# 03-_-.net
KiCad netlist of a schematic drawn in Altium Designer
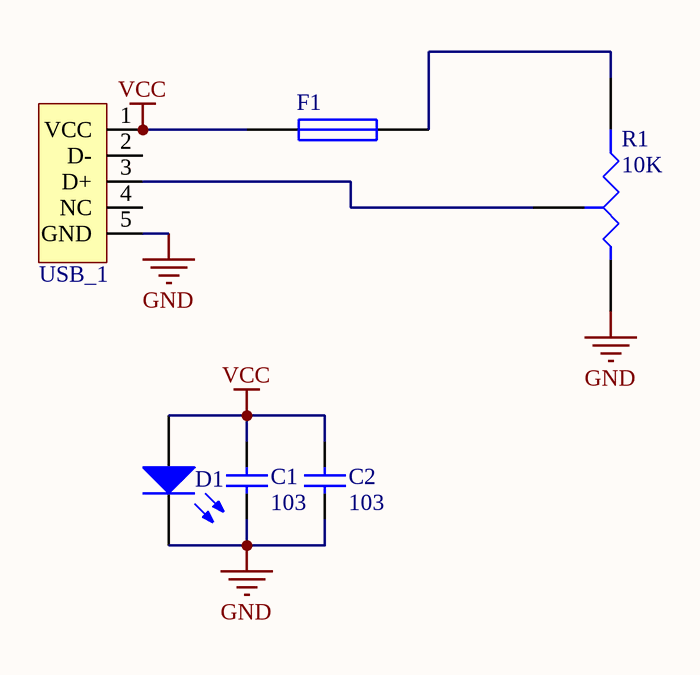
[diagram p0: 03-旋钮模块-原理图.SchDoc]

(export (version "E")
  (design (tool "Eeschema 10.0.6"))
  (components
    (comp (ref "C1")
      (value "103")
      (footprint "0805")
      (description "Capacitor")
      (fields (field (name "Comment") "Cap") (field (name "PUBLISHER") "Altium Limited"))
      (libsource (lib "Miscellaneous Devices") (part "Cap"))
    )
    (comp (ref "C2")
      (value "103")
      (footprint "0805")
      (description "Capacitor")
      (fields (field (name "Comment") "Cap") (field (name "PUBLISHER") "Altium Limited"))
      (libsource (lib "Miscellaneous Devices") (part "Cap"))
    )
    (comp (ref "D1")
      (value "LED0")
      (footprint "0805")
      (description "Typical INFRARED GaAs LED")
      (fields (field (name "PUBLISHER") "Altium Limited"))
      (libsource (lib "Miscellaneous Devices") (part "LED0"))
    )
    (comp (ref "F1")
      (value "Fuse 1")
      (footprint "Fuse")
      (description "Fuse")
      (fields (field (name "PUBLISHER") "Altium Limited"))
      (libsource (lib "Miscellaneous Devices") (part "Fuse 1"))
    )
    (comp (ref "R1")
      (value "10K")
      (footprint "滑动电阻器")
      (description "Tapped Resistor")
      (fields (field (name "Comment") "Res Tap") (field (name "PUBLISHER") "Altium Limited"))
      (libsource (lib "Miscellaneous Devices") (part "Res Tap"))
    )
    (comp (ref "USB_1") (value "USB") (footprint "USB/SM0.8-6H5") (libsource (lib "原理图库") (part "USB5")))
  )
  (nets
    (net (code "1") (name "GND") (class "Default")
      (node (ref "C1") (pin "2") (pinfunction "2_2") (pintype "passive"))
      (node (ref "C2") (pin "2") (pinfunction "2_2") (pintype "passive"))
      (node (ref "D1") (pin "2") (pinfunction "K_2") (pintype "passive"))
      (node (ref "R1") (pin "1") (pinfunction "A_1") (pintype "passive"))
      (node (ref "USB_1") (pin "5") (pinfunction "GND_5") (pintype "passive"))
    )
    (net (code "2") (name "Net-(R1-B)") (class "Default")
      (node (ref "F1") (pin "2") (pinfunction "2_2") (pintype "passive"))
      (node (ref "R1") (pin "2") (pinfunction "B_2") (pintype "passive"))
    )
    (net (code "3") (name "Net-(R1-TAP)") (class "Default")
      (node (ref "R1") (pin "3") (pinfunction "TAP_3") (pintype "passive"))
      (node (ref "USB_1") (pin "3") (pinfunction "D+_3") (pintype "passive"))
    )
    (net (code "4") (name "VCC") (class "Default")
      (node (ref "C1") (pin "1") (pinfunction "1_1") (pintype "passive"))
      (node (ref "C2") (pin "1") (pinfunction "1_1") (pintype "passive"))
      (node (ref "D1") (pin "1") (pinfunction "A_1") (pintype "passive"))
      (node (ref "F1") (pin "1") (pinfunction "1_1") (pintype "passive"))
      (node (ref "USB_1") (pin "1") (pinfunction "VCC_1") (pintype "passive"))
    )
    (net (code "5") (name "unconnected-(USB_1-D--Pad2)") (class "Default")
      (node (ref "USB_1") (pin "2") (pinfunction "D-_2") (pintype "passive"))
    )
    (net (code "6") (name "unconnected-(USB_1-NC-Pad4)") (class "Default")
      (node (ref "USB_1") (pin "4") (pinfunction "NC_4") (pintype "passive"))
    )
  )
)
